# processorboard.net
KiCad netlist of a schematic drawn in EAGLE
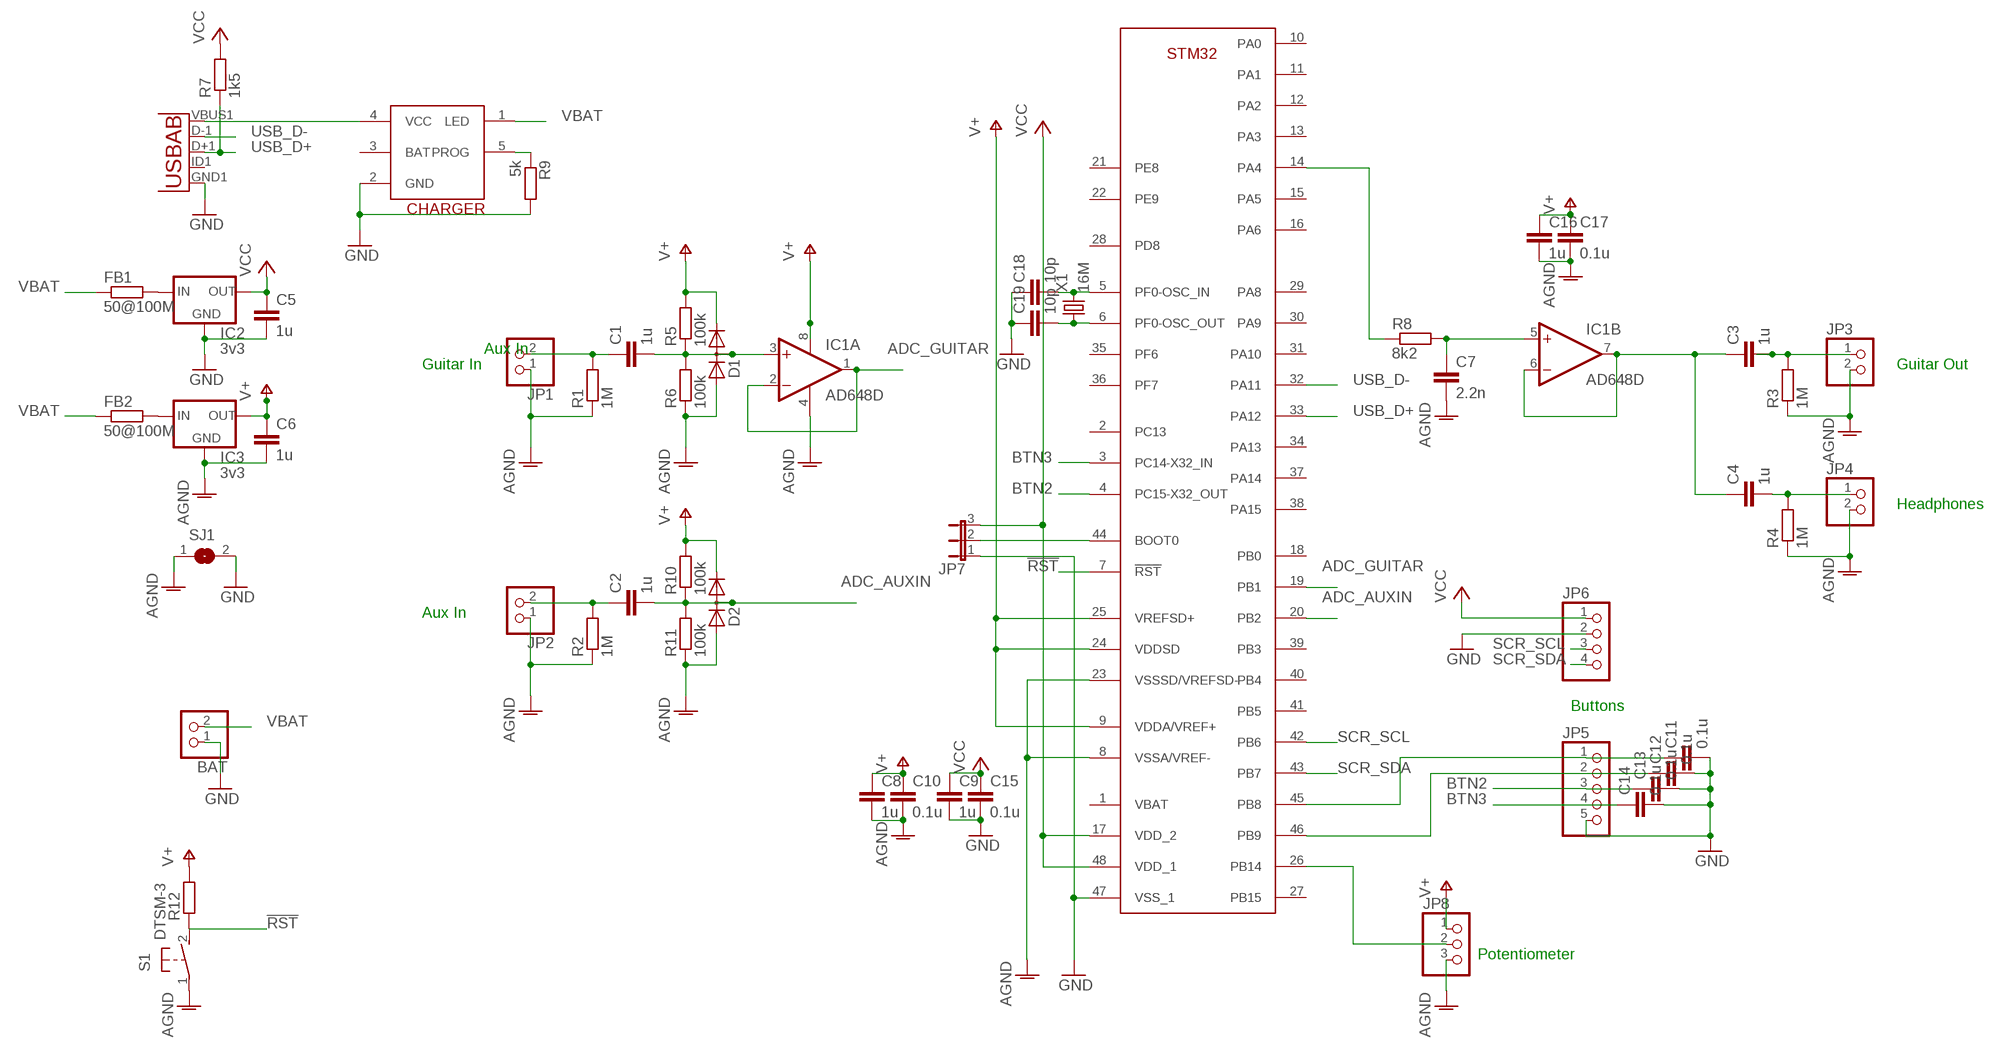
[diagram p0: schematic, sheet 1]

(export (version "E")
  (design (tool "Eeschema 10.0.6"))
  (components
    (comp (ref "BAT")
      (value "PINHD-1X2")
      (footprint "eagle-import:1X02")
      (libsource (lib "eagle-import") (part "PINHD-1X2"))
    )
    (comp (ref "C1")
      (value "1u")
      (footprint "eagle-import:C0805")
      (libsource (lib "eagle-import") (part "C-EUC0805"))
    )
    (comp (ref "C2")
      (value "1u")
      (footprint "eagle-import:C0805")
      (libsource (lib "eagle-import") (part "C-EUC0805"))
    )
    (comp (ref "C3")
      (value "1u")
      (footprint "eagle-import:C0805")
      (libsource (lib "eagle-import") (part "C-EUC0805"))
    )
    (comp (ref "C4")
      (value "1u")
      (footprint "eagle-import:C0805")
      (libsource (lib "eagle-import") (part "C-EUC0805"))
    )
    (comp (ref "C5")
      (value "1u")
      (footprint "eagle-import:C0805")
      (libsource (lib "eagle-import") (part "C-EUC0805"))
    )
    (comp (ref "C6")
      (value "1u")
      (footprint "eagle-import:C0805")
      (libsource (lib "eagle-import") (part "C-EUC0805"))
    )
    (comp (ref "C7")
      (value "2.2n")
      (footprint "eagle-import:C0805")
      (libsource (lib "eagle-import") (part "C-EUC0805"))
    )
    (comp (ref "C8")
      (value "1u")
      (footprint "eagle-import:C0805")
      (libsource (lib "eagle-import") (part "C-EUC0805"))
    )
    (comp (ref "C9")
      (value "1u")
      (footprint "eagle-import:C0805")
      (libsource (lib "eagle-import") (part "C-EUC0805"))
    )
    (comp (ref "C10")
      (value "0.1u")
      (footprint "eagle-import:C0805")
      (libsource (lib "eagle-import") (part "C-EUC0805"))
    )
    (comp (ref "C11")
      (value "0.1u")
      (footprint "eagle-import:C0805")
      (libsource (lib "eagle-import") (part "C-EUC0805"))
    )
    (comp (ref "C12")
      (value "0.1u")
      (footprint "eagle-import:C0805")
      (libsource (lib "eagle-import") (part "C-EUC0805"))
    )
    (comp (ref "C13")
      (value "0.1u")
      (footprint "eagle-import:C0805")
      (libsource (lib "eagle-import") (part "C-EUC0805"))
    )
    (comp (ref "C14")
      (value "0.1u")
      (footprint "eagle-import:C0805")
      (libsource (lib "eagle-import") (part "C-EUC0805"))
    )
    (comp (ref "C15")
      (value "0.1u")
      (footprint "eagle-import:C0805")
      (libsource (lib "eagle-import") (part "C-EUC0805"))
    )
    (comp (ref "C16")
      (value "1u")
      (footprint "eagle-import:C0805")
      (libsource (lib "eagle-import") (part "C-EUC0805"))
    )
    (comp (ref "C17")
      (value "0.1u")
      (footprint "eagle-import:C0805")
      (libsource (lib "eagle-import") (part "C-EUC0805"))
    )
    (comp (ref "C18")
      (value "10p")
      (footprint "eagle-import:C0805")
      (libsource (lib "eagle-import") (part "C-EUC0805"))
    )
    (comp (ref "C19")
      (value "10p")
      (footprint "eagle-import:C0805")
      (libsource (lib "eagle-import") (part "C-EUC0805"))
    )
    (comp (ref "D1")
      (value "DIODE_2CACA-SOT23")
      (footprint "eagle-import:SOT23")
      (libsource (lib "eagle-import") (part "DIODE_2CACA-SOT23"))
    )
    (comp (ref "D2")
      (value "DIODE_2CACA-SOT23")
      (footprint "eagle-import:SOT23")
      (libsource (lib "eagle-import") (part "DIODE_2CACA-SOT23"))
    )
    (comp (ref "FB1")
      (value "50@100M")
      (footprint "eagle-import:R0805")
      (libsource (lib "eagle-import") (part "R-EU_R0805"))
    )
    (comp (ref "FB2")
      (value "50@100M")
      (footprint "eagle-import:R0805")
      (libsource (lib "eagle-import") (part "R-EU_R0805"))
    )
    (comp (ref "IC1")
      (value "AD648D")
      (footprint "eagle-import:SO08")
      (libsource (lib "eagle-import") (part "AD648D"))
    )
    (comp (ref "IC2")
      (value "3v3")
      (footprint "eagle-import:SOT23")
      (libsource (lib "eagle-import") (part "XC63FPM"))
    )
    (comp (ref "IC3")
      (value "3v3")
      (footprint "eagle-import:SOT23")
      (libsource (lib "eagle-import") (part "XC63FPM"))
    )
    (comp (ref "JP1")
      (value "PINHD-1X2")
      (footprint "eagle-import:1X02")
      (libsource (lib "eagle-import") (part "PINHD-1X2"))
    )
    (comp (ref "JP2")
      (value "PINHD-1X2")
      (footprint "eagle-import:1X02")
      (libsource (lib "eagle-import") (part "PINHD-1X2"))
    )
    (comp (ref "JP3")
      (value "PINHD-1X2")
      (footprint "eagle-import:1X02")
      (libsource (lib "eagle-import") (part "PINHD-1X2"))
    )
    (comp (ref "JP4")
      (value "PINHD-1X2")
      (footprint "eagle-import:1X02")
      (libsource (lib "eagle-import") (part "PINHD-1X2"))
    )
    (comp (ref "JP5")
      (value "PINHD-1X5")
      (footprint "eagle-import:1X05")
      (libsource (lib "eagle-import") (part "PINHD-1X5"))
    )
    (comp (ref "JP6")
      (value "PINHD-1X4")
      (footprint "eagle-import:1X04")
      (libsource (lib "eagle-import") (part "PINHD-1X4"))
    )
    (comp (ref "JP7")
      (value "JP2E")
      (footprint "eagle-import:JP2")
      (libsource (lib "eagle-import") (part "JP2E"))
    )
    (comp (ref "JP8")
      (value "PINHD-1X3")
      (footprint "eagle-import:1X03")
      (libsource (lib "eagle-import") (part "PINHD-1X3"))
    )
    (comp (ref "R1")
      (value "1M")
      (footprint "eagle-import:R0805")
      (libsource (lib "eagle-import") (part "R-EU_R0805"))
    )
    (comp (ref "R2")
      (value "1M")
      (footprint "eagle-import:R0805")
      (libsource (lib "eagle-import") (part "R-EU_R0805"))
    )
    (comp (ref "R3")
      (value "1M")
      (footprint "eagle-import:R0805")
      (libsource (lib "eagle-import") (part "R-EU_R0805"))
    )
    (comp (ref "R4")
      (value "1M")
      (footprint "eagle-import:R0805")
      (libsource (lib "eagle-import") (part "R-EU_R0805"))
    )
    (comp (ref "R5")
      (value "100k")
      (footprint "eagle-import:R0805")
      (libsource (lib "eagle-import") (part "R-EU_R0805"))
    )
    (comp (ref "R6")
      (value "100k")
      (footprint "eagle-import:R0805")
      (libsource (lib "eagle-import") (part "R-EU_R0805"))
    )
    (comp (ref "R7")
      (value "1k5")
      (footprint "eagle-import:R0805")
      (libsource (lib "eagle-import") (part "R-EU_R0805"))
    )
    (comp (ref "R8")
      (value "8k2")
      (footprint "eagle-import:R0805")
      (libsource (lib "eagle-import") (part "R-EU_R0805"))
    )
    (comp (ref "R9")
      (value "5k")
      (footprint "eagle-import:R0805")
      (libsource (lib "eagle-import") (part "R-EU_R0805"))
    )
    (comp (ref "R10")
      (value "100k")
      (footprint "eagle-import:R0805")
      (libsource (lib "eagle-import") (part "R-EU_R0805"))
    )
    (comp (ref "R11")
      (value "100k")
      (footprint "eagle-import:R0805")
      (libsource (lib "eagle-import") (part "R-EU_R0805"))
    )
    (comp (ref "R12")
      (value "R-EU_R0805")
      (footprint "eagle-import:R0805")
      (libsource (lib "eagle-import") (part "R-EU_R0805"))
    )
    (comp (ref "S1")
      (value "DTSM-3")
      (footprint "eagle-import:DTSM-3")
      (libsource (lib "eagle-import") (part "DTSM-3"))
    )
    (comp (ref "SJ1") (value "SJ") (footprint "eagle-import:SJ") (libsource (lib "eagle-import") (part "SJ")))
    (comp (ref "U$1")
      (value "STM32F373CBT6")
      (footprint "eagle-import:LQFP48")
      (libsource (lib "eagle-import") (part "STM32F373CBT6"))
    )
    (comp (ref "U$2")
      (value "LI_CHARGER")
      (footprint "eagle-import:SOT23-5L")
      (libsource (lib "eagle-import") (part "LI_CHARGER"))
    )
    (comp (ref "U1")
      (value "USB\"\"")
      (footprint "eagle-import:USB-MICRO-SMD")
      (libsource (lib "eagle-import") (part "USB{dblquote}{dblquote}"))
    )
    (comp (ref "X1")
      (value "16M")
      (footprint "eagle-import:HC49UP")
      (libsource (lib "eagle-import") (part "CRYSTALHC49UP"))
    )
  )
  (nets
    (net (code "1") (name "/ADC_AUXIN") (class "Default")
      (node (ref "C2") (pin "2") (pinfunction "2_2") (pintype "passive"))
      (node (ref "D2") (pin "3") (pinfunction "AC_3") (pintype "passive"))
      (node (ref "R10") (pin "1") (pinfunction "1_1") (pintype "passive"))
      (node (ref "R11") (pin "2") (pinfunction "2_2") (pintype "passive"))
      (node (ref "U$1") (pin "20") (pinfunction "PB2_20") (pintype "bidirectional"))
    )
    (net (code "2") (name "/ADC_GUITAR") (class "Default")
      (node (ref "IC1") (pin "1") (pinfunction "OUT_1") (pintype "output"))
      (node (ref "IC1") (pin "2") (pinfunction "-IN_2") (pintype "input"))
      (node (ref "U$1") (pin "19") (pinfunction "PB1_19") (pintype "bidirectional"))
    )
    (net (code "3") (name "/BTN2") (class "Default")
      (node (ref "C13") (pin "1") (pinfunction "1_1") (pintype "passive"))
      (node (ref "JP5") (pin "3") (pinfunction "3_3") (pintype "passive"))
      (node (ref "U$1") (pin "4") (pinfunction "PC15-X32_OUT_4") (pintype "bidirectional"))
    )
    (net (code "4") (name "/BTN3") (class "Default")
      (node (ref "C14") (pin "1") (pinfunction "1_1") (pintype "passive"))
      (node (ref "JP5") (pin "4") (pinfunction "4_4") (pintype "passive"))
      (node (ref "U$1") (pin "3") (pinfunction "PC14-X32_IN_3") (pintype "bidirectional"))
    )
    (net (code "5") (name "/SCR_SCL") (class "Default")
      (node (ref "JP6") (pin "3") (pinfunction "3_3") (pintype "passive"))
      (node (ref "U$1") (pin "42") (pinfunction "PB6_42") (pintype "bidirectional"))
    )
    (net (code "6") (name "/SCR_SDA") (class "Default")
      (node (ref "JP6") (pin "4") (pinfunction "4_4") (pintype "passive"))
      (node (ref "U$1") (pin "43") (pinfunction "PB7_43") (pintype "bidirectional"))
    )
    (net (code "7") (name "/USB_D+") (class "Default")
      (node (ref "R7") (pin "1") (pinfunction "1_1") (pintype "passive"))
      (node (ref "U$1") (pin "33") (pinfunction "PA12_33") (pintype "bidirectional"))
      (node (ref "U1") (pin "D+1") (pinfunction "D+_D+1") (pintype "bidirectional"))
    )
    (net (code "8") (name "/USB_D-") (class "Default")
      (node (ref "U$1") (pin "32") (pinfunction "PA11_32") (pintype "bidirectional"))
      (node (ref "U1") (pin "D-1") (pinfunction "D-_D-1") (pintype "bidirectional"))
    )
    (net (code "9") (name "/VBAT") (class "Default")
      (node (ref "BAT") (pin "2") (pinfunction "2_2") (pintype "passive"))
      (node (ref "FB1") (pin "1") (pinfunction "1_1") (pintype "passive"))
      (node (ref "FB2") (pin "1") (pinfunction "1_1") (pintype "passive"))
      (node (ref "U$2") (pin "1") (pinfunction "LED_1") (pintype "bidirectional"))
    )
    (net (code "10") (name "/~{RST}") (class "Default")
      (node (ref "R12") (pin "1") (pinfunction "1_1") (pintype "passive"))
      (node (ref "S1") (pin "2") (pinfunction "2_2") (pintype "passive"))
      (node (ref "U$1") (pin "7") (pinfunction "~{RST}_7") (pintype "bidirectional"))
    )
    (net (code "11") (name "AGND") (class "Default")
      (node (ref "C10") (pin "2") (pinfunction "2_2") (pintype "passive"))
      (node (ref "C16") (pin "2") (pinfunction "2_2") (pintype "passive"))
      (node (ref "C17") (pin "2") (pinfunction "2_2") (pintype "passive"))
      (node (ref "C6") (pin "2") (pinfunction "2_2") (pintype "passive"))
      (node (ref "C7") (pin "2") (pinfunction "2_2") (pintype "passive"))
      (node (ref "C8") (pin "2") (pinfunction "2_2") (pintype "passive"))
      (node (ref "D1") (pin "1") (pinfunction "A_1") (pintype "passive"))
      (node (ref "D2") (pin "1") (pinfunction "A_1") (pintype "passive"))
      (node (ref "IC1") (pin "4") (pinfunction "V-_4") (pintype "power_in"))
      (node (ref "IC3") (pin "1") (pinfunction "GND_1") (pintype "input"))
      (node (ref "JP1") (pin "1") (pinfunction "1_1") (pintype "passive"))
      (node (ref "JP2") (pin "1") (pinfunction "1_1") (pintype "passive"))
      (node (ref "JP3") (pin "2") (pinfunction "2_2") (pintype "passive"))
      (node (ref "JP4") (pin "2") (pinfunction "2_2") (pintype "passive"))
      (node (ref "JP8") (pin "3") (pinfunction "3_3") (pintype "passive"))
      (node (ref "R1") (pin "1") (pinfunction "1_1") (pintype "passive"))
      (node (ref "R11") (pin "1") (pinfunction "1_1") (pintype "passive"))
      (node (ref "R2") (pin "1") (pinfunction "1_1") (pintype "passive"))
      (node (ref "R3") (pin "1") (pinfunction "1_1") (pintype "passive"))
      (node (ref "R4") (pin "1") (pinfunction "1_1") (pintype "passive"))
      (node (ref "R6") (pin "1") (pinfunction "1_1") (pintype "passive"))
      (node (ref "S1") (pin "1") (pinfunction "1_1") (pintype "passive"))
      (node (ref "SJ1") (pin "1") (pinfunction "1_1") (pintype "passive"))
      (node (ref "U$1") (pin "23") (pinfunction "VSSSD/VREFSD-_23") (pintype "bidirectional"))
      (node (ref "U$1") (pin "8") (pinfunction "VSSA/VREF-_8") (pintype "bidirectional"))
    )
    (net (code "12") (name "GND") (class "Default")
      (node (ref "BAT") (pin "1") (pinfunction "1_1") (pintype "passive"))
      (node (ref "C11") (pin "2") (pinfunction "2_2") (pintype "passive"))
      (node (ref "C12") (pin "2") (pinfunction "2_2") (pintype "passive"))
      (node (ref "C13") (pin "2") (pinfunction "2_2") (pintype "passive"))
      (node (ref "C14") (pin "2") (pinfunction "2_2") (pintype "passive"))
      (node (ref "C15") (pin "2") (pinfunction "2_2") (pintype "passive"))
      (node (ref "C18") (pin "1") (pinfunction "1_1") (pintype "passive"))
      (node (ref "C19") (pin "1") (pinfunction "1_1") (pintype "passive"))
      (node (ref "C5") (pin "2") (pinfunction "2_2") (pintype "passive"))
      (node (ref "C9") (pin "2") (pinfunction "2_2") (pintype "passive"))
      (node (ref "IC2") (pin "1") (pinfunction "GND_1") (pintype "input"))
      (node (ref "JP5") (pin "5") (pinfunction "5_5") (pintype "passive"))
      (node (ref "JP6") (pin "2") (pinfunction "2_2") (pintype "passive"))
      (node (ref "JP7") (pin "1") (pinfunction "1_1") (pintype "passive"))
      (node (ref "R9") (pin "2") (pinfunction "2_2") (pintype "passive"))
      (node (ref "SJ1") (pin "2") (pinfunction "2_2") (pintype "passive"))
      (node (ref "U$1") (pin "47") (pinfunction "VSS_1_47") (pintype "bidirectional"))
      (node (ref "U$2") (pin "2") (pinfunction "GND_2") (pintype "bidirectional"))
      (node (ref "U1") (pin "GND1") (pinfunction "GND_GND1") (pintype "bidirectional"))
    )
    (net (code "13") (name "Net-(C1-Pad1)") (class "Default")
      (node (ref "C1") (pin "1") (pinfunction "1_1") (pintype "passive"))
      (node (ref "JP1") (pin "2") (pinfunction "2_2") (pintype "passive"))
      (node (ref "R1") (pin "2") (pinfunction "2_2") (pintype "passive"))
    )
    (net (code "14") (name "Net-(C2-Pad1)") (class "Default")
      (node (ref "C2") (pin "1") (pinfunction "1_1") (pintype "passive"))
      (node (ref "JP2") (pin "2") (pinfunction "2_2") (pintype "passive"))
      (node (ref "R2") (pin "2") (pinfunction "2_2") (pintype "passive"))
    )
    (net (code "15") (name "Net-(C3-Pad2)") (class "Default")
      (node (ref "C3") (pin "2") (pinfunction "2_2") (pintype "passive"))
      (node (ref "JP3") (pin "1") (pinfunction "1_1") (pintype "passive"))
      (node (ref "R3") (pin "2") (pinfunction "2_2") (pintype "passive"))
    )
    (net (code "16") (name "Net-(C4-Pad2)") (class "Default")
      (node (ref "C4") (pin "2") (pinfunction "2_2") (pintype "passive"))
      (node (ref "JP4") (pin "1") (pinfunction "1_1") (pintype "passive"))
      (node (ref "R4") (pin "2") (pinfunction "2_2") (pintype "passive"))
    )
    (net (code "17") (name "Net-(D1-AC)") (class "Default")
      (node (ref "C1") (pin "2") (pinfunction "2_2") (pintype "passive"))
      (node (ref "D1") (pin "3") (pinfunction "AC_3") (pintype "passive"))
      (node (ref "IC1") (pin "3") (pinfunction "+IN_3") (pintype "input"))
      (node (ref "R5") (pin "1") (pinfunction "1_1") (pintype "passive"))
      (node (ref "R6") (pin "2") (pinfunction "2_2") (pintype "passive"))
    )
    (net (code "18") (name "Net-(IC1B-+IN)") (class "Default")
      (node (ref "C7") (pin "1") (pinfunction "1_1") (pintype "passive"))
      (node (ref "IC1") (pin "5") (pinfunction "+IN_5") (pintype "input"))
      (node (ref "R8") (pin "2") (pinfunction "2_2") (pintype "passive"))
    )
    (net (code "19") (name "Net-(IC1B--IN)") (class "Default")
      (node (ref "C3") (pin "1") (pinfunction "1_1") (pintype "passive"))
      (node (ref "C4") (pin "1") (pinfunction "1_1") (pintype "passive"))
      (node (ref "IC1") (pin "6") (pinfunction "-IN_6") (pintype "input"))
      (node (ref "IC1") (pin "7") (pinfunction "OUT_7") (pintype "output"))
    )
    (net (code "20") (name "Net-(IC2-IN)") (class "Default")
      (node (ref "FB1") (pin "2") (pinfunction "2_2") (pintype "passive"))
      (node (ref "IC2") (pin "3") (pinfunction "IN_3") (pintype "input"))
    )
    (net (code "21") (name "Net-(IC3-IN)") (class "Default")
      (node (ref "FB2") (pin "2") (pinfunction "2_2") (pintype "passive"))
      (node (ref "IC3") (pin "3") (pinfunction "IN_3") (pintype "input"))
    )
    (net (code "22") (name "Net-(U$1-BOOT0)") (class "Default")
      (node (ref "JP7") (pin "2") (pinfunction "2_2") (pintype "passive"))
      (node (ref "U$1") (pin "44") (pinfunction "BOOT0_44") (pintype "bidirectional"))
    )
    (net (code "23") (name "Net-(U$1-PA4)") (class "Default")
      (node (ref "R8") (pin "1") (pinfunction "1_1") (pintype "passive"))
      (node (ref "U$1") (pin "14") (pinfunction "PA4_14") (pintype "bidirectional"))
    )
    (net (code "24") (name "Net-(U$1-PB8)") (class "Default")
      (node (ref "C11") (pin "1") (pinfunction "1_1") (pintype "passive"))
      (node (ref "JP5") (pin "1") (pinfunction "1_1") (pintype "passive"))
      (node (ref "U$1") (pin "45") (pinfunction "PB8_45") (pintype "bidirectional"))
    )
    (net (code "25") (name "Net-(U$1-PB9)") (class "Default")
      (node (ref "C12") (pin "1") (pinfunction "1_1") (pintype "passive"))
      (node (ref "JP5") (pin "2") (pinfunction "2_2") (pintype "passive"))
      (node (ref "U$1") (pin "46") (pinfunction "PB9_46") (pintype "bidirectional"))
    )
    (net (code "26") (name "Net-(U$1-PB14)") (class "Default")
      (node (ref "JP8") (pin "2") (pinfunction "2_2") (pintype "passive"))
      (node (ref "U$1") (pin "26") (pinfunction "PB14_26") (pintype "bidirectional"))
    )
    (net (code "27") (name "Net-(U$1-PF0-OSC_IN)") (class "Default")
      (node (ref "C18") (pin "2") (pinfunction "2_2") (pintype "passive"))
      (node (ref "U$1") (pin "5") (pinfunction "PF0-OSC_IN_5") (pintype "bidirectional"))
      (node (ref "X1") (pin "2") (pinfunction "2_2") (pintype "passive"))
    )
    (net (code "28") (name "Net-(U$1-PF0-OSC_OUT)") (class "Default")
      (node (ref "C19") (pin "2") (pinfunction "2_2") (pintype "passive"))
      (node (ref "U$1") (pin "6") (pinfunction "PF0-OSC_OUT_6") (pintype "bidirectional"))
      (node (ref "X1") (pin "1") (pinfunction "1_1") (pintype "passive"))
    )
    (net (code "29") (name "Net-(U$2-PROG)") (class "Default")
      (node (ref "R9") (pin "1") (pinfunction "1_1") (pintype "passive"))
      (node (ref "U$2") (pin "5") (pinfunction "PROG_5") (pintype "bidirectional"))
    )
    (net (code "30") (name "Net-(U$2-VCC)") (class "Default")
      (node (ref "U$2") (pin "4") (pinfunction "VCC_4") (pintype "bidirectional"))
      (node (ref "U1") (pin "VBUS1") (pinfunction "VBUS_VBUS1") (pintype "bidirectional"))
    )
    (net (code "31") (name "V+") (class "Default")
      (node (ref "C10") (pin "1") (pinfunction "1_1") (pintype "passive"))
      (node (ref "C16") (pin "1") (pinfunction "1_1") (pintype "passive"))
      (node (ref "C17") (pin "1") (pinfunction "1_1") (pintype "passive"))
      (node (ref "C6") (pin "1") (pinfunction "1_1") (pintype "passive"))
      (node (ref "C8") (pin "1") (pinfunction "1_1") (pintype "passive"))
      (node (ref "D1") (pin "2") (pinfunction "C_2") (pintype "passive"))
      (node (ref "D2") (pin "2") (pinfunction "C_2") (pintype "passive"))
      (node (ref "IC1") (pin "8") (pinfunction "V+_8") (pintype "power_in"))
      (node (ref "IC3") (pin "2") (pinfunction "OUT_2") (pintype "passive"))
      (node (ref "JP8") (pin "1") (pinfunction "1_1") (pintype "passive"))
      (node (ref "R10") (pin "2") (pinfunction "2_2") (pintype "passive"))
      (node (ref "R12") (pin "2") (pinfunction "2_2") (pintype "passive"))
      (node (ref "R5") (pin "2") (pinfunction "2_2") (pintype "passive"))
      (node (ref "U$1") (pin "24") (pinfunction "VDDSD_24") (pintype "bidirectional"))
      (node (ref "U$1") (pin "25") (pinfunction "VREFSD+_25") (pintype "bidirectional"))
      (node (ref "U$1") (pin "9") (pinfunction "VDDA/VREF+_9") (pintype "bidirectional"))
    )
    (net (code "32") (name "VCC") (class "Default")
      (node (ref "C15") (pin "1") (pinfunction "1_1") (pintype "passive"))
      (node (ref "C5") (pin "1") (pinfunction "1_1") (pintype "passive"))
      (node (ref "C9") (pin "1") (pinfunction "1_1") (pintype "passive"))
      (node (ref "IC2") (pin "2") (pinfunction "OUT_2") (pintype "passive"))
      (node (ref "JP6") (pin "1") (pinfunction "1_1") (pintype "passive"))
      (node (ref "JP7") (pin "3") (pinfunction "3_3") (pintype "passive"))
      (node (ref "R7") (pin "2") (pinfunction "2_2") (pintype "passive"))
      (node (ref "U$1") (pin "17") (pinfunction "VDD_2_17") (pintype "bidirectional"))
      (node (ref "U$1") (pin "48") (pinfunction "VDD_1_48") (pintype "bidirectional"))
    )
    (net (code "33") (name "unconnected-(U$1-PA0-Pad10)") (class "Default")
      (node (ref "U$1") (pin "10") (pinfunction "PA0_10") (pintype "bidirectional"))
    )
    (net (code "34") (name "unconnected-(U$1-PA1-Pad11)") (class "Default")
      (node (ref "U$1") (pin "11") (pinfunction "PA1_11") (pintype "bidirectional"))
    )
    (net (code "35") (name "unconnected-(U$1-PA2-Pad12)") (class "Default")
      (node (ref "U$1") (pin "12") (pinfunction "PA2_12") (pintype "bidirectional"))
    )
    (net (code "36") (name "unconnected-(U$1-PA3-Pad13)") (class "Default")
      (node (ref "U$1") (pin "13") (pinfunction "PA3_13") (pintype "bidirectional"))
    )
    (net (code "37") (name "unconnected-(U$1-PA5-Pad15)") (class "Default")
      (node (ref "U$1") (pin "15") (pinfunction "PA5_15") (pintype "bidirectional"))
    )
    (net (code "38") (name "unconnected-(U$1-PA6-Pad16)") (class "Default")
      (node (ref "U$1") (pin "16") (pinfunction "PA6_16") (pintype "bidirectional"))
    )
    (net (code "39") (name "unconnected-(U$1-PA8-Pad29)") (class "Default")
      (node (ref "U$1") (pin "29") (pinfunction "PA8_29") (pintype "bidirectional"))
    )
    (net (code "40") (name "unconnected-(U$1-PA9-Pad30)") (class "Default")
      (node (ref "U$1") (pin "30") (pinfunction "PA9_30") (pintype "bidirectional"))
    )
    (net (code "41") (name "unconnected-(U$1-PA10-Pad31)") (class "Default")
      (node (ref "U$1") (pin "31") (pinfunction "PA10_31") (pintype "bidirectional"))
    )
    (net (code "42") (name "unconnected-(U$1-PA13-Pad34)") (class "Default")
      (node (ref "U$1") (pin "34") (pinfunction "PA13_34") (pintype "bidirectional"))
    )
    (net (code "43") (name "unconnected-(U$1-PA14-Pad37)") (class "Default")
      (node (ref "U$1") (pin "37") (pinfunction "PA14_37") (pintype "bidirectional"))
    )
    (net (code "44") (name "unconnected-(U$1-PA15-Pad38)") (class "Default")
      (node (ref "U$1") (pin "38") (pinfunction "PA15_38") (pintype "bidirectional"))
    )
    (net (code "45") (name "unconnected-(U$1-PB0-Pad18)") (class "Default")
      (node (ref "U$1") (pin "18") (pinfunction "PB0_18") (pintype "bidirectional"))
    )
    (net (code "46") (name "unconnected-(U$1-PB3-Pad39)") (class "Default")
      (node (ref "U$1") (pin "39") (pinfunction "PB3_39") (pintype "bidirectional"))
    )
    (net (code "47") (name "unconnected-(U$1-PB4-Pad40)") (class "Default")
      (node (ref "U$1") (pin "40") (pinfunction "PB4_40") (pintype "bidirectional"))
    )
    (net (code "48") (name "unconnected-(U$1-PB5-Pad41)") (class "Default")
      (node (ref "U$1") (pin "41") (pinfunction "PB5_41") (pintype "bidirectional"))
    )
    (net (code "49") (name "unconnected-(U$1-PB15-Pad27)") (class "Default")
      (node (ref "U$1") (pin "27") (pinfunction "PB15_27") (pintype "bidirectional"))
    )
    (net (code "50") (name "unconnected-(U$1-PC13-Pad2)") (class "Default")
      (node (ref "U$1") (pin "2") (pinfunction "PC13_2") (pintype "bidirectional"))
    )
    (net (code "51") (name "unconnected-(U$1-PD8-Pad28)") (class "Default")
      (node (ref "U$1") (pin "28") (pinfunction "PD8_28") (pintype "bidirectional"))
    )
    (net (code "52") (name "unconnected-(U$1-PE8-Pad21)") (class "Default")
      (node (ref "U$1") (pin "21") (pinfunction "PE8_21") (pintype "bidirectional"))
    )
    (net (code "53") (name "unconnected-(U$1-PE9-Pad22)") (class "Default")
      (node (ref "U$1") (pin "22") (pinfunction "PE9_22") (pintype "bidirectional"))
    )
    (net (code "54") (name "unconnected-(U$1-PF6-Pad35)") (class "Default")
      (node (ref "U$1") (pin "35") (pinfunction "PF6_35") (pintype "bidirectional"))
    )
    (net (code "55") (name "unconnected-(U$1-PF7-Pad36)") (class "Default")
      (node (ref "U$1") (pin "36") (pinfunction "PF7_36") (pintype "bidirectional"))
    )
    (net (code "56") (name "unconnected-(U$1-VBAT-Pad1)") (class "Default")
      (node (ref "U$1") (pin "1") (pinfunction "VBAT_1") (pintype "bidirectional"))
    )
    (net (code "57") (name "unconnected-(U$2-BAT-Pad3)") (class "Default")
      (node (ref "U$2") (pin "3") (pinfunction "BAT_3") (pintype "bidirectional"))
    )
    (net (code "58") (name "unconnected-(U1-USBID-PadID1)") (class "Default")
      (node (ref "U1") (pin "ID1") (pinfunction "USBID_ID1") (pintype "bidirectional"))
    )
  )
)
